# MPU6050.net
KiCad netlist of a schematic drawn in Altium Designer
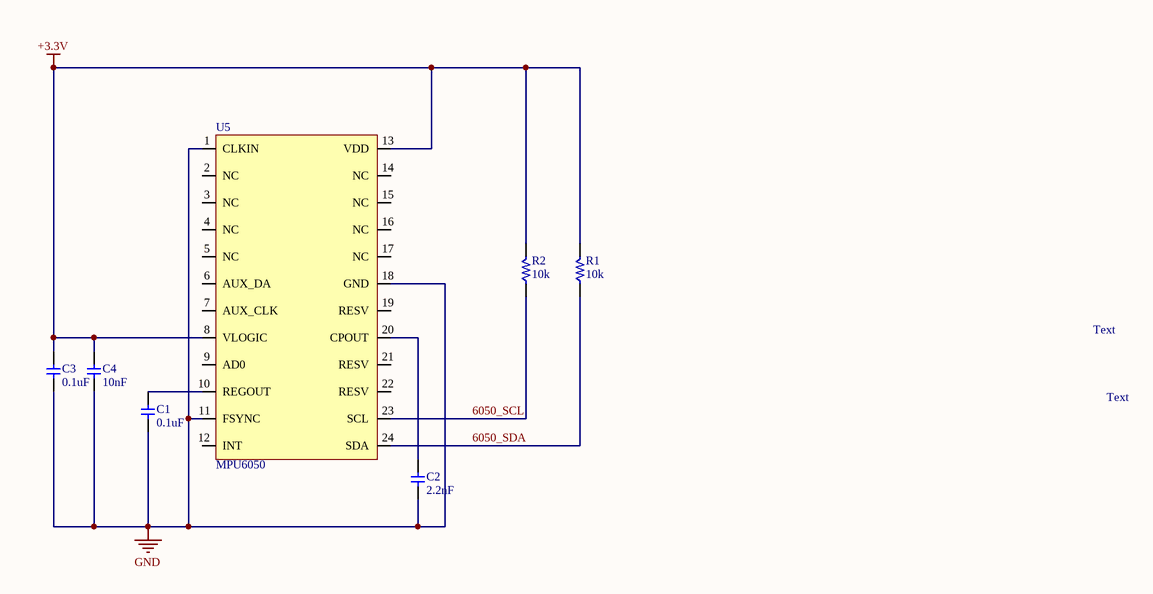
[diagram p0: MPU6050.SchDoc]

(export (version "E")
  (design (tool "Eeschema 10.0.6"))
  (components
    (comp (ref "C1")
      (value "0.1uF")
      (footprint "0805")
      (description "Generic capacitor")
      (fields (field (name "Comment") "Generic Capacitor"))
      (libsource (lib "PowerCircuit") (part "Capacitor"))
    )
    (comp (ref "C2")
      (value "2.2nF")
      (footprint "0805")
      (description "Generic capacitor")
      (fields (field (name "Comment") "Generic Capacitor"))
      (libsource (lib "PowerCircuit") (part "Capacitor"))
    )
    (comp (ref "C3")
      (value "0.1uF")
      (footprint "0805")
      (description "Generic capacitor")
      (fields (field (name "Comment") "Generic Capacitor"))
      (libsource (lib "PowerCircuit") (part "Capacitor"))
    )
    (comp (ref "C4")
      (value "10nF")
      (footprint "0805")
      (description "Generic capacitor")
      (fields (field (name "Comment") "Generic Capacitor"))
      (libsource (lib "PowerCircuit") (part "Capacitor"))
    )
    (comp (ref "R1")
      (value "10k")
      (footprint "0805")
      (description "Generic Resistor")
      (fields (field (name "Comment") "Resistor"))
      (libsource (lib "PowerCircuit") (part "Resistor"))
    )
    (comp (ref "R2")
      (value "10k")
      (footprint "0805")
      (description "Generic Resistor")
      (fields (field (name "Comment") "Resistor"))
      (libsource (lib "PowerCircuit") (part "Resistor"))
    )
    (comp (ref "U5")
      (value "MPU6050")
      (footprint "MPU-6050")
      (description "IMU ACCEL/GYRO 3-AXIS I2C 24QFN")
      (libsource (lib "MPU6050") (part "MPU6050"))
    )
  )
  (nets
    (net (code "1") (name "+3.3V") (class "Default")
      (node (ref "C3") (pin "1") (pinfunction "1_1") (pintype "passive"))
      (node (ref "C4") (pin "2") (pinfunction "2_2") (pintype "passive"))
      (node (ref "R1") (pin "2") (pinfunction "2_2") (pintype "passive"))
      (node (ref "R2") (pin "2") (pinfunction "2_2") (pintype "passive"))
      (node (ref "U5") (pin "13") (pinfunction "VDD_13") (pintype "passive"))
      (node (ref "U5") (pin "8") (pinfunction "VLOGIC_8") (pintype "passive"))
    )
    (net (code "2") (name "/6050_SCL") (class "Default")
      (node (ref "R2") (pin "1") (pinfunction "1_1") (pintype "passive"))
      (node (ref "U5") (pin "23") (pinfunction "SCL_23") (pintype "passive"))
    )
    (net (code "3") (name "/6050_SDA") (class "Default")
      (node (ref "R1") (pin "1") (pinfunction "1_1") (pintype "passive"))
      (node (ref "U5") (pin "24") (pinfunction "SDA_24") (pintype "passive"))
    )
    (net (code "4") (name "GND") (class "Default")
      (node (ref "C1") (pin "1") (pinfunction "1_1") (pintype "passive"))
      (node (ref "C2") (pin "1") (pinfunction "1_1") (pintype "passive"))
      (node (ref "C3") (pin "2") (pinfunction "2_2") (pintype "passive"))
      (node (ref "C4") (pin "1") (pinfunction "1_1") (pintype "passive"))
      (node (ref "U5") (pin "1") (pinfunction "CLKIN_1") (pintype "passive"))
      (node (ref "U5") (pin "11") (pinfunction "FSYNC_11") (pintype "passive"))
      (node (ref "U5") (pin "18") (pinfunction "GND_18") (pintype "passive"))
    )
    (net (code "5") (name "Net-(U5-CPOUT)") (class "Default")
      (node (ref "C2") (pin "2") (pinfunction "2_2") (pintype "passive"))
      (node (ref "U5") (pin "20") (pinfunction "CPOUT_20") (pintype "passive"))
    )
    (net (code "6") (name "Net-(U5-REGOUT)") (class "Default")
      (node (ref "C1") (pin "2") (pinfunction "2_2") (pintype "passive"))
      (node (ref "U5") (pin "10") (pinfunction "REGOUT_10") (pintype "passive"))
    )
    (net (code "7") (name "unconnected-(U5-AD0-Pad9)") (class "Default")
      (node (ref "U5") (pin "9") (pinfunction "AD0_9") (pintype "passive"))
    )
    (net (code "8") (name "unconnected-(U5-AUX_CLK-Pad7)") (class "Default")
      (node (ref "U5") (pin "7") (pinfunction "AUX_CLK_7") (pintype "passive"))
    )
    (net (code "9") (name "unconnected-(U5-AUX_DA-Pad6)") (class "Default")
      (node (ref "U5") (pin "6") (pinfunction "AUX_DA_6") (pintype "passive"))
    )
    (net (code "10") (name "unconnected-(U5-INT-Pad12)") (class "Default")
      (node (ref "U5") (pin "12") (pinfunction "INT_12") (pintype "passive"))
    )
    (net (code "11") (name "unconnected-(U5-NC-Pad2)") (class "Default")
      (node (ref "U5") (pin "2") (pinfunction "NC_2") (pintype "passive"))
    )
    (net (code "12") (name "unconnected-(U5-NC-Pad3)") (class "Default")
      (node (ref "U5") (pin "3") (pinfunction "NC_3") (pintype "passive"))
    )
    (net (code "13") (name "unconnected-(U5-NC-Pad4)") (class "Default")
      (node (ref "U5") (pin "4") (pinfunction "NC_4") (pintype "passive"))
    )
    (net (code "14") (name "unconnected-(U5-NC-Pad5)") (class "Default")
      (node (ref "U5") (pin "5") (pinfunction "NC_5") (pintype "passive"))
    )
    (net (code "15") (name "unconnected-(U5-NC-Pad14)") (class "Default")
      (node (ref "U5") (pin "14") (pinfunction "NC_14") (pintype "passive"))
    )
    (net (code "16") (name "unconnected-(U5-NC-Pad15)") (class "Default")
      (node (ref "U5") (pin "15") (pinfunction "NC_15") (pintype "passive"))
    )
    (net (code "17") (name "unconnected-(U5-NC-Pad16)") (class "Default")
      (node (ref "U5") (pin "16") (pinfunction "NC_16") (pintype "passive"))
    )
    (net (code "18") (name "unconnected-(U5-NC-Pad17)") (class "Default")
      (node (ref "U5") (pin "17") (pinfunction "NC_17") (pintype "passive"))
    )
    (net (code "19") (name "unconnected-(U5-RESV-Pad19)") (class "Default")
      (node (ref "U5") (pin "19") (pinfunction "RESV_19") (pintype "passive"))
    )
    (net (code "20") (name "unconnected-(U5-RESV-Pad21)") (class "Default")
      (node (ref "U5") (pin "21") (pinfunction "RESV_21") (pintype "passive"))
    )
    (net (code "21") (name "unconnected-(U5-RESV-Pad22)") (class "Default")
      (node (ref "U5") (pin "22") (pinfunction "RESV_22") (pintype "passive"))
    )
  )
)
